# Automotive_Connector.net
KiCad netlist of a schematic drawn in Altium Designer
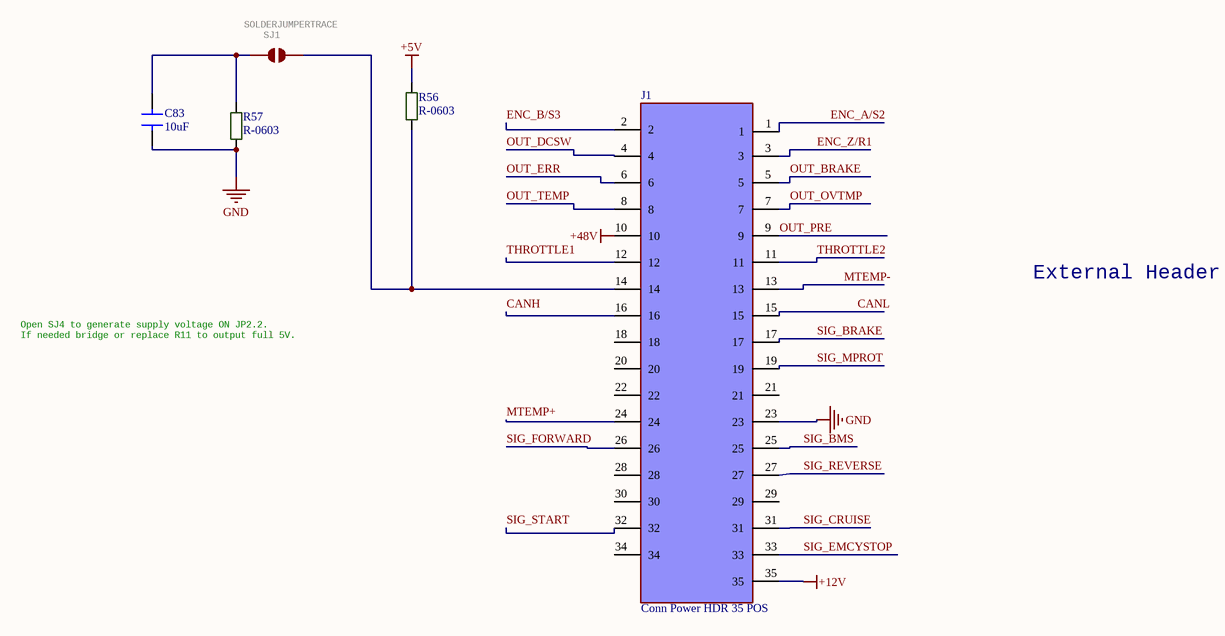
[diagram p0: Automotive Connector.SchDoc]

(export (version "E")
  (design (tool "Eeschema 10.0.6"))
  (components
    (comp (ref "C83")
      (value "10uF")
      (footprint "C-0805")
      (libsource (lib "Gate Driver Board") (part "C-0805"))
    )
    (comp (ref "J1")
      (value "Conn Power HDR 35 POS")
      (footprint "TE_776230-2")
      (description "Conn Power HDR 35 POS 4mm Solder ST Thru-Hole 35 Terminal 1 Port Automotive Loose")
      (fields (field (name "MP") "776230-2") (field (name "MF") "TE Connectivity"))
      (libsource (lib "Gate Driver Board") (part "Conn Power HDR 35 POS"))
    )
    (comp (ref "R56")
      (value "R-0603")
      (footprint "R-0603R")
      (libsource (lib "Gate Driver Board") (part "R-0603"))
    )
    (comp (ref "R57")
      (value "R-0603")
      (footprint "R-0603R")
      (libsource (lib "Gate Driver Board") (part "R-0603"))
    )
    (comp (ref "SJ1")
      (value "SOLDERJUMPERTRACE")
      (footprint "SJ_2S-TRACE")
      (libsource (lib "Gate Driver Board") (part "SOLDERJUMPERTRACE"))
    )
  )
  (nets
    (net (code "1") (name "+5V") (class "Default")
      (node (ref "R56") (pin "2") (pinfunction "2_2") (pintype "passive"))
    )
    (net (code "2") (name "+12V") (class "Default")
      (node (ref "J1") (pin "35") (pinfunction "35_35") (pintype "passive"))
    )
    (net (code "3") (name "+48V") (class "Default")
      (node (ref "J1") (pin "10") (pinfunction "10_10") (pintype "passive"))
    )
    (net (code "4") (name "/CANH") (class "Default")
      (node (ref "J1") (pin "16") (pinfunction "16_16") (pintype "passive"))
    )
    (net (code "5") (name "/CANL") (class "Default")
      (node (ref "J1") (pin "15") (pinfunction "15_15") (pintype "passive"))
    )
    (net (code "6") (name "/ENC_A{slash}S2") (class "Default")
      (node (ref "J1") (pin "1") (pinfunction "1_1") (pintype "passive"))
    )
    (net (code "7") (name "/ENC_B{slash}S3") (class "Default")
      (node (ref "J1") (pin "2") (pinfunction "2_2") (pintype "passive"))
    )
    (net (code "8") (name "/ENC_Z{slash}R1") (class "Default")
      (node (ref "J1") (pin "3") (pinfunction "3_3") (pintype "passive"))
    )
    (net (code "9") (name "/MTEMP+") (class "Default")
      (node (ref "J1") (pin "24") (pinfunction "24_24") (pintype "passive"))
    )
    (net (code "10") (name "/MTEMP-") (class "Default")
      (node (ref "J1") (pin "13") (pinfunction "13_13") (pintype "passive"))
    )
    (net (code "11") (name "/OUT_BRAKE") (class "Default")
      (node (ref "J1") (pin "5") (pinfunction "5_5") (pintype "passive"))
    )
    (net (code "12") (name "/OUT_DCSW") (class "Default")
      (node (ref "J1") (pin "4") (pinfunction "4_4") (pintype "passive"))
    )
    (net (code "13") (name "/OUT_ERR") (class "Default")
      (node (ref "J1") (pin "6") (pinfunction "6_6") (pintype "passive"))
    )
    (net (code "14") (name "/OUT_OVTMP") (class "Default")
      (node (ref "J1") (pin "7") (pinfunction "7_7") (pintype "passive"))
    )
    (net (code "15") (name "/OUT_PRE") (class "Default")
      (node (ref "J1") (pin "9") (pinfunction "9_9") (pintype "passive"))
    )
    (net (code "16") (name "/OUT_TEMP") (class "Default")
      (node (ref "J1") (pin "8") (pinfunction "8_8") (pintype "passive"))
    )
    (net (code "17") (name "/SIG_BMS") (class "Default")
      (node (ref "J1") (pin "25") (pinfunction "25_25") (pintype "passive"))
    )
    (net (code "18") (name "/SIG_BRAKE") (class "Default")
      (node (ref "J1") (pin "17") (pinfunction "17_17") (pintype "passive"))
    )
    (net (code "19") (name "/SIG_CRUISE") (class "Default")
      (node (ref "J1") (pin "31") (pinfunction "31_31") (pintype "passive"))
    )
    (net (code "20") (name "/SIG_EMCYSTOP") (class "Default")
      (node (ref "J1") (pin "33") (pinfunction "33_33") (pintype "passive"))
    )
    (net (code "21") (name "/SIG_FORWARD") (class "Default")
      (node (ref "J1") (pin "26") (pinfunction "26_26") (pintype "passive"))
    )
    (net (code "22") (name "/SIG_MPROT") (class "Default")
      (node (ref "J1") (pin "19") (pinfunction "19_19") (pintype "passive"))
    )
    (net (code "23") (name "/SIG_REVERSE") (class "Default")
      (node (ref "J1") (pin "27") (pinfunction "27_27") (pintype "passive"))
    )
    (net (code "24") (name "/SIG_START") (class "Default")
      (node (ref "J1") (pin "32") (pinfunction "32_32") (pintype "passive"))
    )
    (net (code "25") (name "/THROTTLE1") (class "Default")
      (node (ref "J1") (pin "12") (pinfunction "12_12") (pintype "passive"))
    )
    (net (code "26") (name "/THROTTLE2") (class "Default")
      (node (ref "J1") (pin "11") (pinfunction "11_11") (pintype "passive"))
    )
    (net (code "27") (name "GND") (class "Default")
      (node (ref "C83") (pin "1") (pinfunction "1_1") (pintype "passive"))
      (node (ref "J1") (pin "23") (pinfunction "23_23") (pintype "passive"))
      (node (ref "R57") (pin "1") (pinfunction "1_1") (pintype "passive"))
    )
    (net (code "28") (name "Net-(C83-Pad2)") (class "Default")
      (node (ref "C83") (pin "2") (pinfunction "2_2") (pintype "passive"))
      (node (ref "R57") (pin "2") (pinfunction "2_2") (pintype "passive"))
      (node (ref "SJ1") (pin "1") (pinfunction "1_1") (pintype "passive"))
    )
    (net (code "29") (name "Net-(J1-Pad14)") (class "Default")
      (node (ref "J1") (pin "14") (pinfunction "14_14") (pintype "passive"))
      (node (ref "R56") (pin "1") (pinfunction "1_1") (pintype "passive"))
      (node (ref "SJ1") (pin "2") (pinfunction "2_2") (pintype "passive"))
    )
    (net (code "30") (name "unconnected-(J1-Pad18)") (class "Default")
      (node (ref "J1") (pin "18") (pinfunction "18_18") (pintype "passive"))
    )
    (net (code "31") (name "unconnected-(J1-Pad20)") (class "Default")
      (node (ref "J1") (pin "20") (pinfunction "20_20") (pintype "passive"))
    )
    (net (code "32") (name "unconnected-(J1-Pad21)") (class "Default")
      (node (ref "J1") (pin "21") (pinfunction "21_21") (pintype "passive"))
    )
    (net (code "33") (name "unconnected-(J1-Pad22)") (class "Default")
      (node (ref "J1") (pin "22") (pinfunction "22_22") (pintype "passive"))
    )
    (net (code "34") (name "unconnected-(J1-Pad28)") (class "Default")
      (node (ref "J1") (pin "28") (pinfunction "28_28") (pintype "passive"))
    )
    (net (code "35") (name "unconnected-(J1-Pad29)") (class "Default")
      (node (ref "J1") (pin "29") (pinfunction "29_29") (pintype "passive"))
    )
    (net (code "36") (name "unconnected-(J1-Pad30)") (class "Default")
      (node (ref "J1") (pin "30") (pinfunction "30_30") (pintype "passive"))
    )
    (net (code "37") (name "unconnected-(J1-Pad34)") (class "Default")
      (node (ref "J1") (pin "34") (pinfunction "34_34") (pintype "passive"))
    )
  )
)
